# STM32F030_-_VGA_minimal_v5.net
KiCad netlist of a schematic drawn in EAGLE
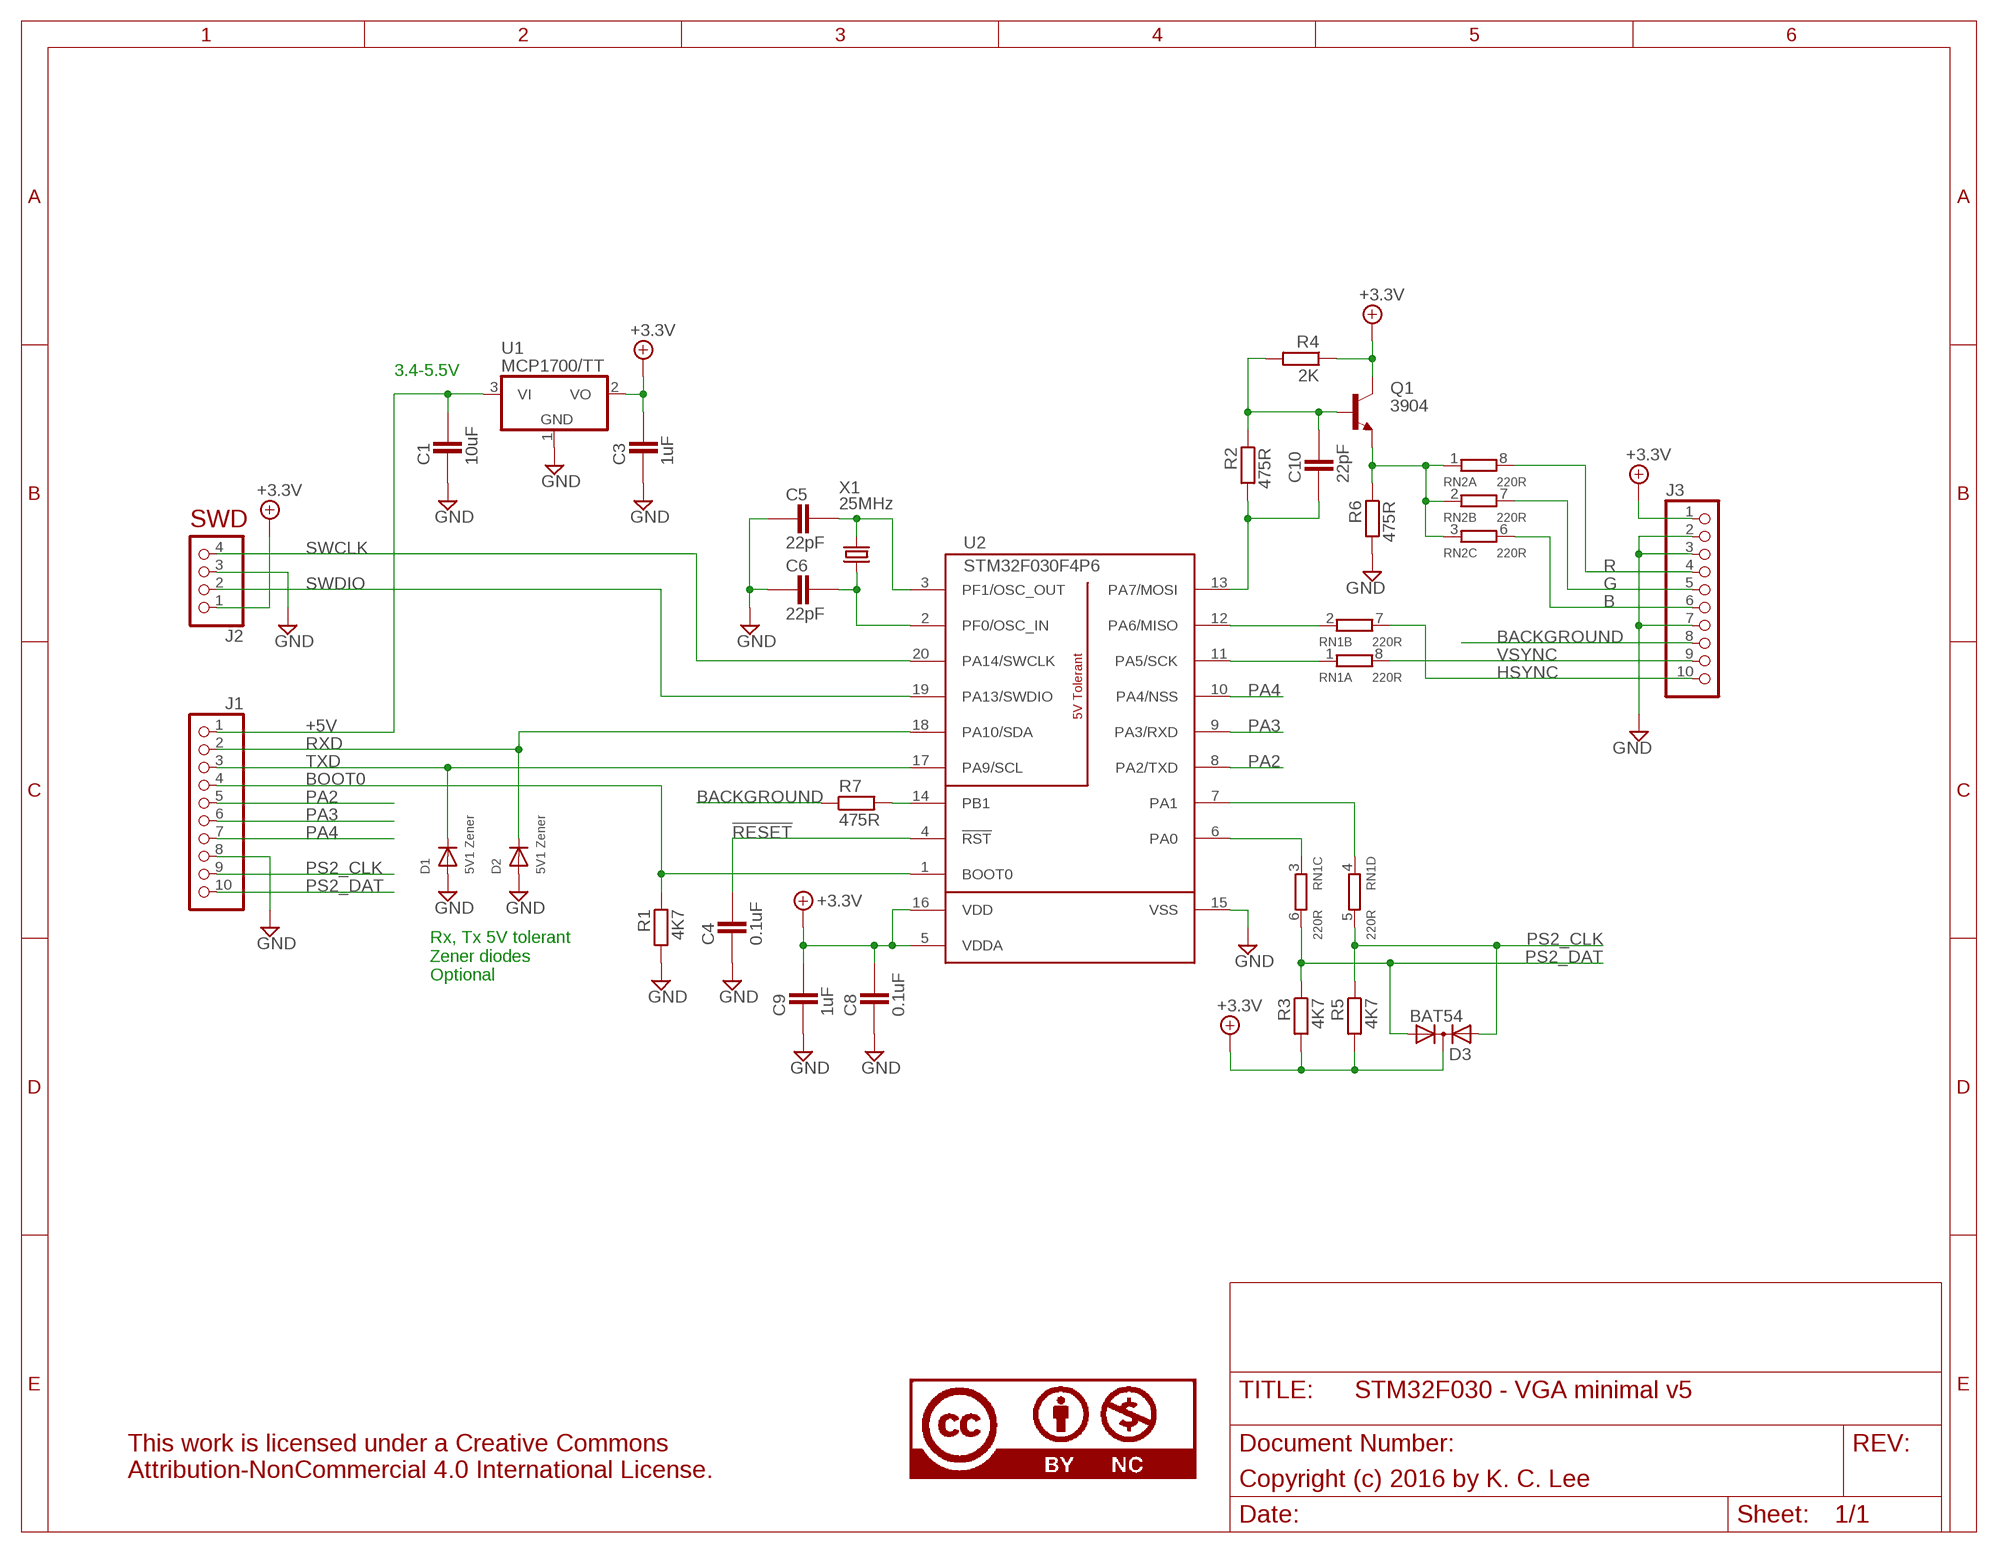
[diagram p0: schematic, sheet 1]

(export (version "E")
  (design (tool "Eeschema 10.0.6"))
  (components
    (comp (ref "C1")
      (value "10uF")
      (footprint "eagle-import:CAPC2012X145AN")
      (fields (field (name "PARTNO") "10UF/10V X5R 0805"))
      (libsource (lib "eagle-import") (part "CAPACITOR_0805"))
    )
    (comp (ref "C3")
      (value "1uF")
      (footprint "eagle-import:CAPC2012X145AN")
      (fields (field (name "PARTNO") "1UF, 0805"))
      (libsource (lib "eagle-import") (part "CAPACITOR_0805"))
    )
    (comp (ref "C4")
      (value "0.1uF")
      (footprint "eagle-import:CAPC1608X92N")
      (fields (field (name "PARTNO") "0.1UF, 0603"))
      (libsource (lib "eagle-import") (part "CAPACITOR_0603"))
    )
    (comp (ref "C5")
      (value "22pF")
      (footprint "eagle-import:CAPC1608X92N")
      (fields (field (name "PARTNO") "22PF, 0603"))
      (libsource (lib "eagle-import") (part "CAPACITOR_0603"))
    )
    (comp (ref "C6")
      (value "22pF")
      (footprint "eagle-import:CAPC1608X92N")
      (fields (field (name "PARTNO") "22PF, 0603"))
      (libsource (lib "eagle-import") (part "CAPACITOR_0603"))
    )
    (comp (ref "C8")
      (value "0.1uF")
      (footprint "eagle-import:CAPC1608X92N")
      (fields (field (name "PARTNO") "0.1UF, 0603"))
      (libsource (lib "eagle-import") (part "CAPACITOR_0603"))
    )
    (comp (ref "C9")
      (value "1uF")
      (footprint "eagle-import:CAPC1608X92N")
      (fields (field (name "PARTNO") "1UF, 0603"))
      (libsource (lib "eagle-import") (part "CAPACITOR_0603"))
    )
    (comp (ref "C10")
      (value "22pF")
      (footprint "eagle-import:CAPC1608X92N")
      (fields (field (name "PARTNO") "22PF, 0603"))
      (libsource (lib "eagle-import") (part "CAPACITOR_0603"))
    )
    (comp (ref "D1")
      (value "5V1 Zener")
      (footprint "eagle-import:SOD-123")
      (fields (field (name "PARTNO") "BZT52C5V1"))
      (libsource (lib "eagle-import") (part "DIODESOD-123"))
    )
    (comp (ref "D2")
      (value "5V1 Zener")
      (footprint "eagle-import:SOD-123")
      (fields (field (name "PARTNO") "BZT52C5V1"))
      (libsource (lib "eagle-import") (part "DIODESOD-123"))
    )
    (comp (ref "D3")
      (value "BAT54")
      (footprint "eagle-import:SOT95P280X135-3N")
      (libsource (lib "eagle-import") (part "A2K_SOT-23"))
    )
    (comp (ref "J1")
      (value "PINHD-1X10")
      (footprint "eagle-import:1X10")
      (fields (field (name "PARTNO") "0.1 IN HEADER 1X10"))
      (libsource (lib "eagle-import") (part "PINHD-1X10"))
    )
    (comp (ref "J2")
      (value "PINHD-1X4_2.54")
      (footprint "eagle-import:1X04")
      (fields (field (name "PARTNO") "0.1 IN HEADER 1X4"))
      (libsource (lib "eagle-import") (part "PINHD-1X4_2.54"))
    )
    (comp (ref "J3")
      (value "PINHD-1X10")
      (footprint "eagle-import:1X10")
      (fields (field (name "PARTNO") "0.1 IN HEADER 1X10"))
      (libsource (lib "eagle-import") (part "PINHD-1X10"))
    )
    (comp (ref "LICENSE")
      (value "CC-BY-NC")
      (footprint "eagle-import:CC-BY-NC-75")
      (fields (field (name "PARTNO") "LICENSE"))
      (libsource (lib "eagle-import") (part "CC-BY-NC75%"))
    )
    (comp (ref "Q1")
      (value "3904")
      (footprint "eagle-import:SOT95P280X135-3N")
      (fields (field (name "PARTNO") "MMBT3904"))
      (libsource (lib "eagle-import") (part "NPN_SOT-23"))
    )
    (comp (ref "R1")
      (value "4K7")
      (footprint "eagle-import:RESC1608X55N")
      (fields (field (name "PARTNO") "4K7, 0603"))
      (libsource (lib "eagle-import") (part "RESISTOR_0603"))
    )
    (comp (ref "R2")
      (value "475R")
      (footprint "eagle-import:RESC1608X55N")
      (fields (field (name "PARTNO") "475R, 0603"))
      (libsource (lib "eagle-import") (part "RESISTOR_0603"))
    )
    (comp (ref "R3")
      (value "4K7")
      (footprint "eagle-import:RESC1608X55N")
      (fields (field (name "PARTNO") "4K7, 0603"))
      (libsource (lib "eagle-import") (part "RESISTOR_0603"))
    )
    (comp (ref "R4")
      (value "2K")
      (footprint "eagle-import:RESC1608X55N")
      (fields (field (name "PARTNO") "2K, 0603"))
      (libsource (lib "eagle-import") (part "RESISTOR_0603"))
    )
    (comp (ref "R5")
      (value "4K7")
      (footprint "eagle-import:RESC1608X55N")
      (fields (field (name "PARTNO") "4K7, 0603"))
      (libsource (lib "eagle-import") (part "RESISTOR_0603"))
    )
    (comp (ref "R6")
      (value "475R")
      (footprint "eagle-import:RESC1608X55N")
      (fields (field (name "PARTNO") "475R, 0603"))
      (libsource (lib "eagle-import") (part "RESISTOR_0603"))
    )
    (comp (ref "R7")
      (value "475R")
      (footprint "eagle-import:RESC1608X55N")
      (fields (field (name "PARTNO") "475R, 0603"))
      (libsource (lib "eagle-import") (part "RESISTOR_0603"))
    )
    (comp (ref "RN1")
      (value "220R")
      (footprint "eagle-import:CAT16")
      (fields (field (name "PARTNO") "CAT16-221J4"))
      (libsource (lib "eagle-import") (part "4R-NCAT16"))
    )
    (comp (ref "RN2")
      (value "220R")
      (footprint "eagle-import:CAT16")
      (fields (field (name "PARTNO") "CAT16-221J4"))
      (libsource (lib "eagle-import") (part "4R-NCAT16"))
    )
    (comp (ref "U1")
      (value "MCP1700/TT")
      (footprint "eagle-import:SOT95P280X135-3N")
      (fields (field (name "PARTNO") "MCP1700T-3302E/TT"))
      (libsource (lib "eagle-import") (part "MCP1700/TT"))
    )
    (comp (ref "U2")
      (value "STM32F030F4P6")
      (footprint "eagle-import:TSSOP20")
      (libsource (lib "eagle-import") (part "STM32F030F4P6"))
    )
    (comp (ref "X1")
      (value "25MHz")
      (footprint "eagle-import:SM49")
      (fields (field (name "PARTNO") "25MHZ FUND. HC49"))
      (libsource (lib "eagle-import") (part "CRYSTALSM49"))
    )
  )
  (nets
    (net (code "1") (name "+3.3V") (class "Default")
      (node (ref "C3") (pin "2") (pinfunction "2_2") (pintype "passive"))
      (node (ref "C8") (pin "2") (pinfunction "2_2") (pintype "passive"))
      (node (ref "C9") (pin "2") (pinfunction "2_2") (pintype "passive"))
      (node (ref "D3") (pin "3") (pinfunction "K_3") (pintype "passive"))
      (node (ref "J2") (pin "1") (pinfunction "1_1") (pintype "passive"))
      (node (ref "J3") (pin "1") (pinfunction "1_1") (pintype "passive"))
      (node (ref "Q1") (pin "3") (pinfunction "C_3") (pintype "passive"))
      (node (ref "R3") (pin "2") (pinfunction "2_2") (pintype "passive"))
      (node (ref "R4") (pin "1") (pinfunction "1_1") (pintype "passive"))
      (node (ref "R5") (pin "2") (pinfunction "2_2") (pintype "passive"))
      (node (ref "U1") (pin "2") (pinfunction "VO_2") (pintype "passive"))
      (node (ref "U2") (pin "16") (pinfunction "VDD_16") (pintype "input"))
      (node (ref "U2") (pin "5") (pinfunction "VDDA_5") (pintype "input"))
    )
    (net (code "2") (name "/+5V") (class "Default")
      (node (ref "C1") (pin "2") (pinfunction "2_2") (pintype "passive"))
      (node (ref "J1") (pin "1") (pinfunction "1_1") (pintype "passive"))
      (node (ref "U1") (pin "3") (pinfunction "VI_3") (pintype "input"))
    )
    (net (code "3") (name "/B") (class "Default")
      (node (ref "J3") (pin "6") (pinfunction "6_6") (pintype "passive"))
      (node (ref "RN2") (pin "6") (pinfunction "2_6") (pintype "passive"))
    )
    (net (code "4") (name "/BACKGROUND") (class "Default")
      (node (ref "J3") (pin "8") (pinfunction "8_8") (pintype "passive"))
      (node (ref "R7") (pin "1") (pinfunction "1_1") (pintype "passive"))
    )
    (net (code "5") (name "/BOOT0") (class "Default")
      (node (ref "J1") (pin "4") (pinfunction "4_4") (pintype "passive"))
      (node (ref "R1") (pin "1") (pinfunction "1_1") (pintype "passive"))
      (node (ref "U2") (pin "1") (pinfunction "BOOT0_1") (pintype "input"))
    )
    (net (code "6") (name "/G") (class "Default")
      (node (ref "J3") (pin "5") (pinfunction "5_5") (pintype "passive"))
      (node (ref "RN2") (pin "7") (pinfunction "2_7") (pintype "passive"))
    )
    (net (code "7") (name "/HSYNC") (class "Default")
      (node (ref "J3") (pin "10") (pinfunction "10_10") (pintype "passive"))
      (node (ref "RN1") (pin "7") (pinfunction "2_7") (pintype "passive"))
    )
    (net (code "8") (name "/PA2") (class "Default")
      (node (ref "J1") (pin "5") (pinfunction "5_5") (pintype "passive"))
      (node (ref "U2") (pin "8") (pinfunction "PA2/TXD_8") (pintype "bidirectional"))
    )
    (net (code "9") (name "/PA3") (class "Default")
      (node (ref "J1") (pin "6") (pinfunction "6_6") (pintype "passive"))
      (node (ref "U2") (pin "9") (pinfunction "PA3/RXD_9") (pintype "bidirectional"))
    )
    (net (code "10") (name "/PA4") (class "Default")
      (node (ref "J1") (pin "7") (pinfunction "7_7") (pintype "passive"))
      (node (ref "U2") (pin "10") (pinfunction "PA4/NSS_10") (pintype "bidirectional"))
    )
    (net (code "11") (name "/PS2_CLK") (class "Default")
      (node (ref "D3") (pin "2") (pinfunction "A2_2") (pintype "passive"))
      (node (ref "J1") (pin "9") (pinfunction "9_9") (pintype "passive"))
      (node (ref "R5") (pin "1") (pinfunction "1_1") (pintype "passive"))
      (node (ref "RN1") (pin "5") (pinfunction "2_5") (pintype "passive"))
    )
    (net (code "12") (name "/PS2_DAT") (class "Default")
      (node (ref "D3") (pin "1") (pinfunction "A1_1") (pintype "passive"))
      (node (ref "J1") (pin "10") (pinfunction "10_10") (pintype "passive"))
      (node (ref "R3") (pin "1") (pinfunction "1_1") (pintype "passive"))
      (node (ref "RN1") (pin "6") (pinfunction "2_6") (pintype "passive"))
    )
    (net (code "13") (name "/R") (class "Default")
      (node (ref "J3") (pin "4") (pinfunction "4_4") (pintype "passive"))
      (node (ref "RN2") (pin "8") (pinfunction "2_8") (pintype "passive"))
    )
    (net (code "14") (name "/RXD") (class "Default")
      (node (ref "D2") (pin "C") (pinfunction "C_C") (pintype "passive"))
      (node (ref "J1") (pin "2") (pinfunction "2_2") (pintype "passive"))
      (node (ref "U2") (pin "18") (pinfunction "PA10/SDA_18") (pintype "bidirectional"))
    )
    (net (code "15") (name "/SWCLK") (class "Default")
      (node (ref "J2") (pin "4") (pinfunction "4_4") (pintype "passive"))
      (node (ref "U2") (pin "20") (pinfunction "PA14/SWCLK_20") (pintype "bidirectional"))
    )
    (net (code "16") (name "/SWDIO") (class "Default")
      (node (ref "J2") (pin "2") (pinfunction "2_2") (pintype "passive"))
      (node (ref "U2") (pin "19") (pinfunction "PA13/SWDIO_19") (pintype "bidirectional"))
    )
    (net (code "17") (name "/TXD") (class "Default")
      (node (ref "D1") (pin "C") (pinfunction "C_C") (pintype "passive"))
      (node (ref "J1") (pin "3") (pinfunction "3_3") (pintype "passive"))
      (node (ref "U2") (pin "17") (pinfunction "PA9/SCL_17") (pintype "bidirectional"))
    )
    (net (code "18") (name "/VSYNC") (class "Default")
      (node (ref "J3") (pin "9") (pinfunction "9_9") (pintype "passive"))
      (node (ref "RN1") (pin "8") (pinfunction "2_8") (pintype "passive"))
    )
    (net (code "19") (name "/~{RESET}") (class "Default")
      (node (ref "C4") (pin "2") (pinfunction "2_2") (pintype "passive"))
      (node (ref "U2") (pin "4") (pinfunction "~{RST}_4") (pintype "input"))
    )
    (net (code "20") (name "GND") (class "Default")
      (node (ref "C1") (pin "1") (pinfunction "1_1") (pintype "passive"))
      (node (ref "C3") (pin "1") (pinfunction "1_1") (pintype "passive"))
      (node (ref "C4") (pin "1") (pinfunction "1_1") (pintype "passive"))
      (node (ref "C5") (pin "1") (pinfunction "1_1") (pintype "passive"))
      (node (ref "C6") (pin "1") (pinfunction "1_1") (pintype "passive"))
      (node (ref "C8") (pin "1") (pinfunction "1_1") (pintype "passive"))
      (node (ref "C9") (pin "1") (pinfunction "1_1") (pintype "passive"))
      (node (ref "D1") (pin "A") (pinfunction "A_A") (pintype "passive"))
      (node (ref "D2") (pin "A") (pinfunction "A_A") (pintype "passive"))
      (node (ref "J1") (pin "8") (pinfunction "8_8") (pintype "passive"))
      (node (ref "J2") (pin "3") (pinfunction "3_3") (pintype "passive"))
      (node (ref "J3") (pin "2") (pinfunction "2_2") (pintype "passive"))
      (node (ref "J3") (pin "3") (pinfunction "3_3") (pintype "passive"))
      (node (ref "J3") (pin "7") (pinfunction "7_7") (pintype "passive"))
      (node (ref "R1") (pin "2") (pinfunction "2_2") (pintype "passive"))
      (node (ref "R6") (pin "2") (pinfunction "2_2") (pintype "passive"))
      (node (ref "U1") (pin "1") (pinfunction "GND_1") (pintype "passive"))
      (node (ref "U2") (pin "15") (pinfunction "VSS_15") (pintype "input"))
    )
    (net (code "21") (name "Net-(Q1-B)") (class "Default")
      (node (ref "C10") (pin "2") (pinfunction "2_2") (pintype "passive"))
      (node (ref "Q1") (pin "1") (pinfunction "B_1") (pintype "passive"))
      (node (ref "R2") (pin "1") (pinfunction "1_1") (pintype "passive"))
      (node (ref "R4") (pin "2") (pinfunction "2_2") (pintype "passive"))
    )
    (net (code "22") (name "Net-(Q1-E)") (class "Default")
      (node (ref "Q1") (pin "2") (pinfunction "E_2") (pintype "passive"))
      (node (ref "R6") (pin "1") (pinfunction "1_1") (pintype "passive"))
      (node (ref "RN2") (pin "1") (pinfunction "1_1") (pintype "passive"))
      (node (ref "RN2") (pin "2") (pinfunction "1_2") (pintype "passive"))
      (node (ref "RN2") (pin "3") (pinfunction "1_3") (pintype "passive"))
    )
    (net (code "23") (name "Net-(RN1B-1)") (class "Default")
      (node (ref "RN1") (pin "2") (pinfunction "1_2") (pintype "passive"))
      (node (ref "U2") (pin "12") (pinfunction "PA6/MISO_12") (pintype "bidirectional"))
    )
    (net (code "24") (name "Net-(RN1C-1)") (class "Default")
      (node (ref "RN1") (pin "3") (pinfunction "1_3") (pintype "passive"))
      (node (ref "U2") (pin "6") (pinfunction "PA0_6") (pintype "bidirectional"))
    )
    (net (code "25") (name "Net-(RN1D-1)") (class "Default")
      (node (ref "RN1") (pin "4") (pinfunction "1_4") (pintype "passive"))
      (node (ref "U2") (pin "7") (pinfunction "PA1_7") (pintype "bidirectional"))
    )
    (net (code "26") (name "Net-(U2-PA5{slash}SCK)") (class "Default")
      (node (ref "RN1") (pin "1") (pinfunction "1_1") (pintype "passive"))
      (node (ref "U2") (pin "11") (pinfunction "PA5/SCK_11") (pintype "bidirectional"))
    )
    (net (code "27") (name "Net-(U2-PA7{slash}MOSI)") (class "Default")
      (node (ref "C10") (pin "1") (pinfunction "1_1") (pintype "passive"))
      (node (ref "R2") (pin "2") (pinfunction "2_2") (pintype "passive"))
      (node (ref "U2") (pin "13") (pinfunction "PA7/MOSI_13") (pintype "bidirectional"))
    )
    (net (code "28") (name "Net-(U2-PB1)") (class "Default")
      (node (ref "R7") (pin "2") (pinfunction "2_2") (pintype "passive"))
      (node (ref "U2") (pin "14") (pinfunction "PB1_14") (pintype "bidirectional"))
    )
    (net (code "29") (name "Net-(U2-PF0{slash}OSC_IN)") (class "Default")
      (node (ref "C6") (pin "2") (pinfunction "2_2") (pintype "passive"))
      (node (ref "U2") (pin "2") (pinfunction "PF0/OSC_IN_2") (pintype "input"))
      (node (ref "X1") (pin "1") (pinfunction "1_1") (pintype "passive"))
    )
    (net (code "30") (name "Net-(U2-PF1{slash}OSC_OUT)") (class "Default")
      (node (ref "C5") (pin "2") (pinfunction "2_2") (pintype "passive"))
      (node (ref "U2") (pin "3") (pinfunction "PF1/OSC_OUT_3") (pintype "output"))
      (node (ref "X1") (pin "2") (pinfunction "2_2") (pintype "passive"))
    )
  )
)
